# AnyKey.net
KiCad netlist of a schematic drawn in EAGLE
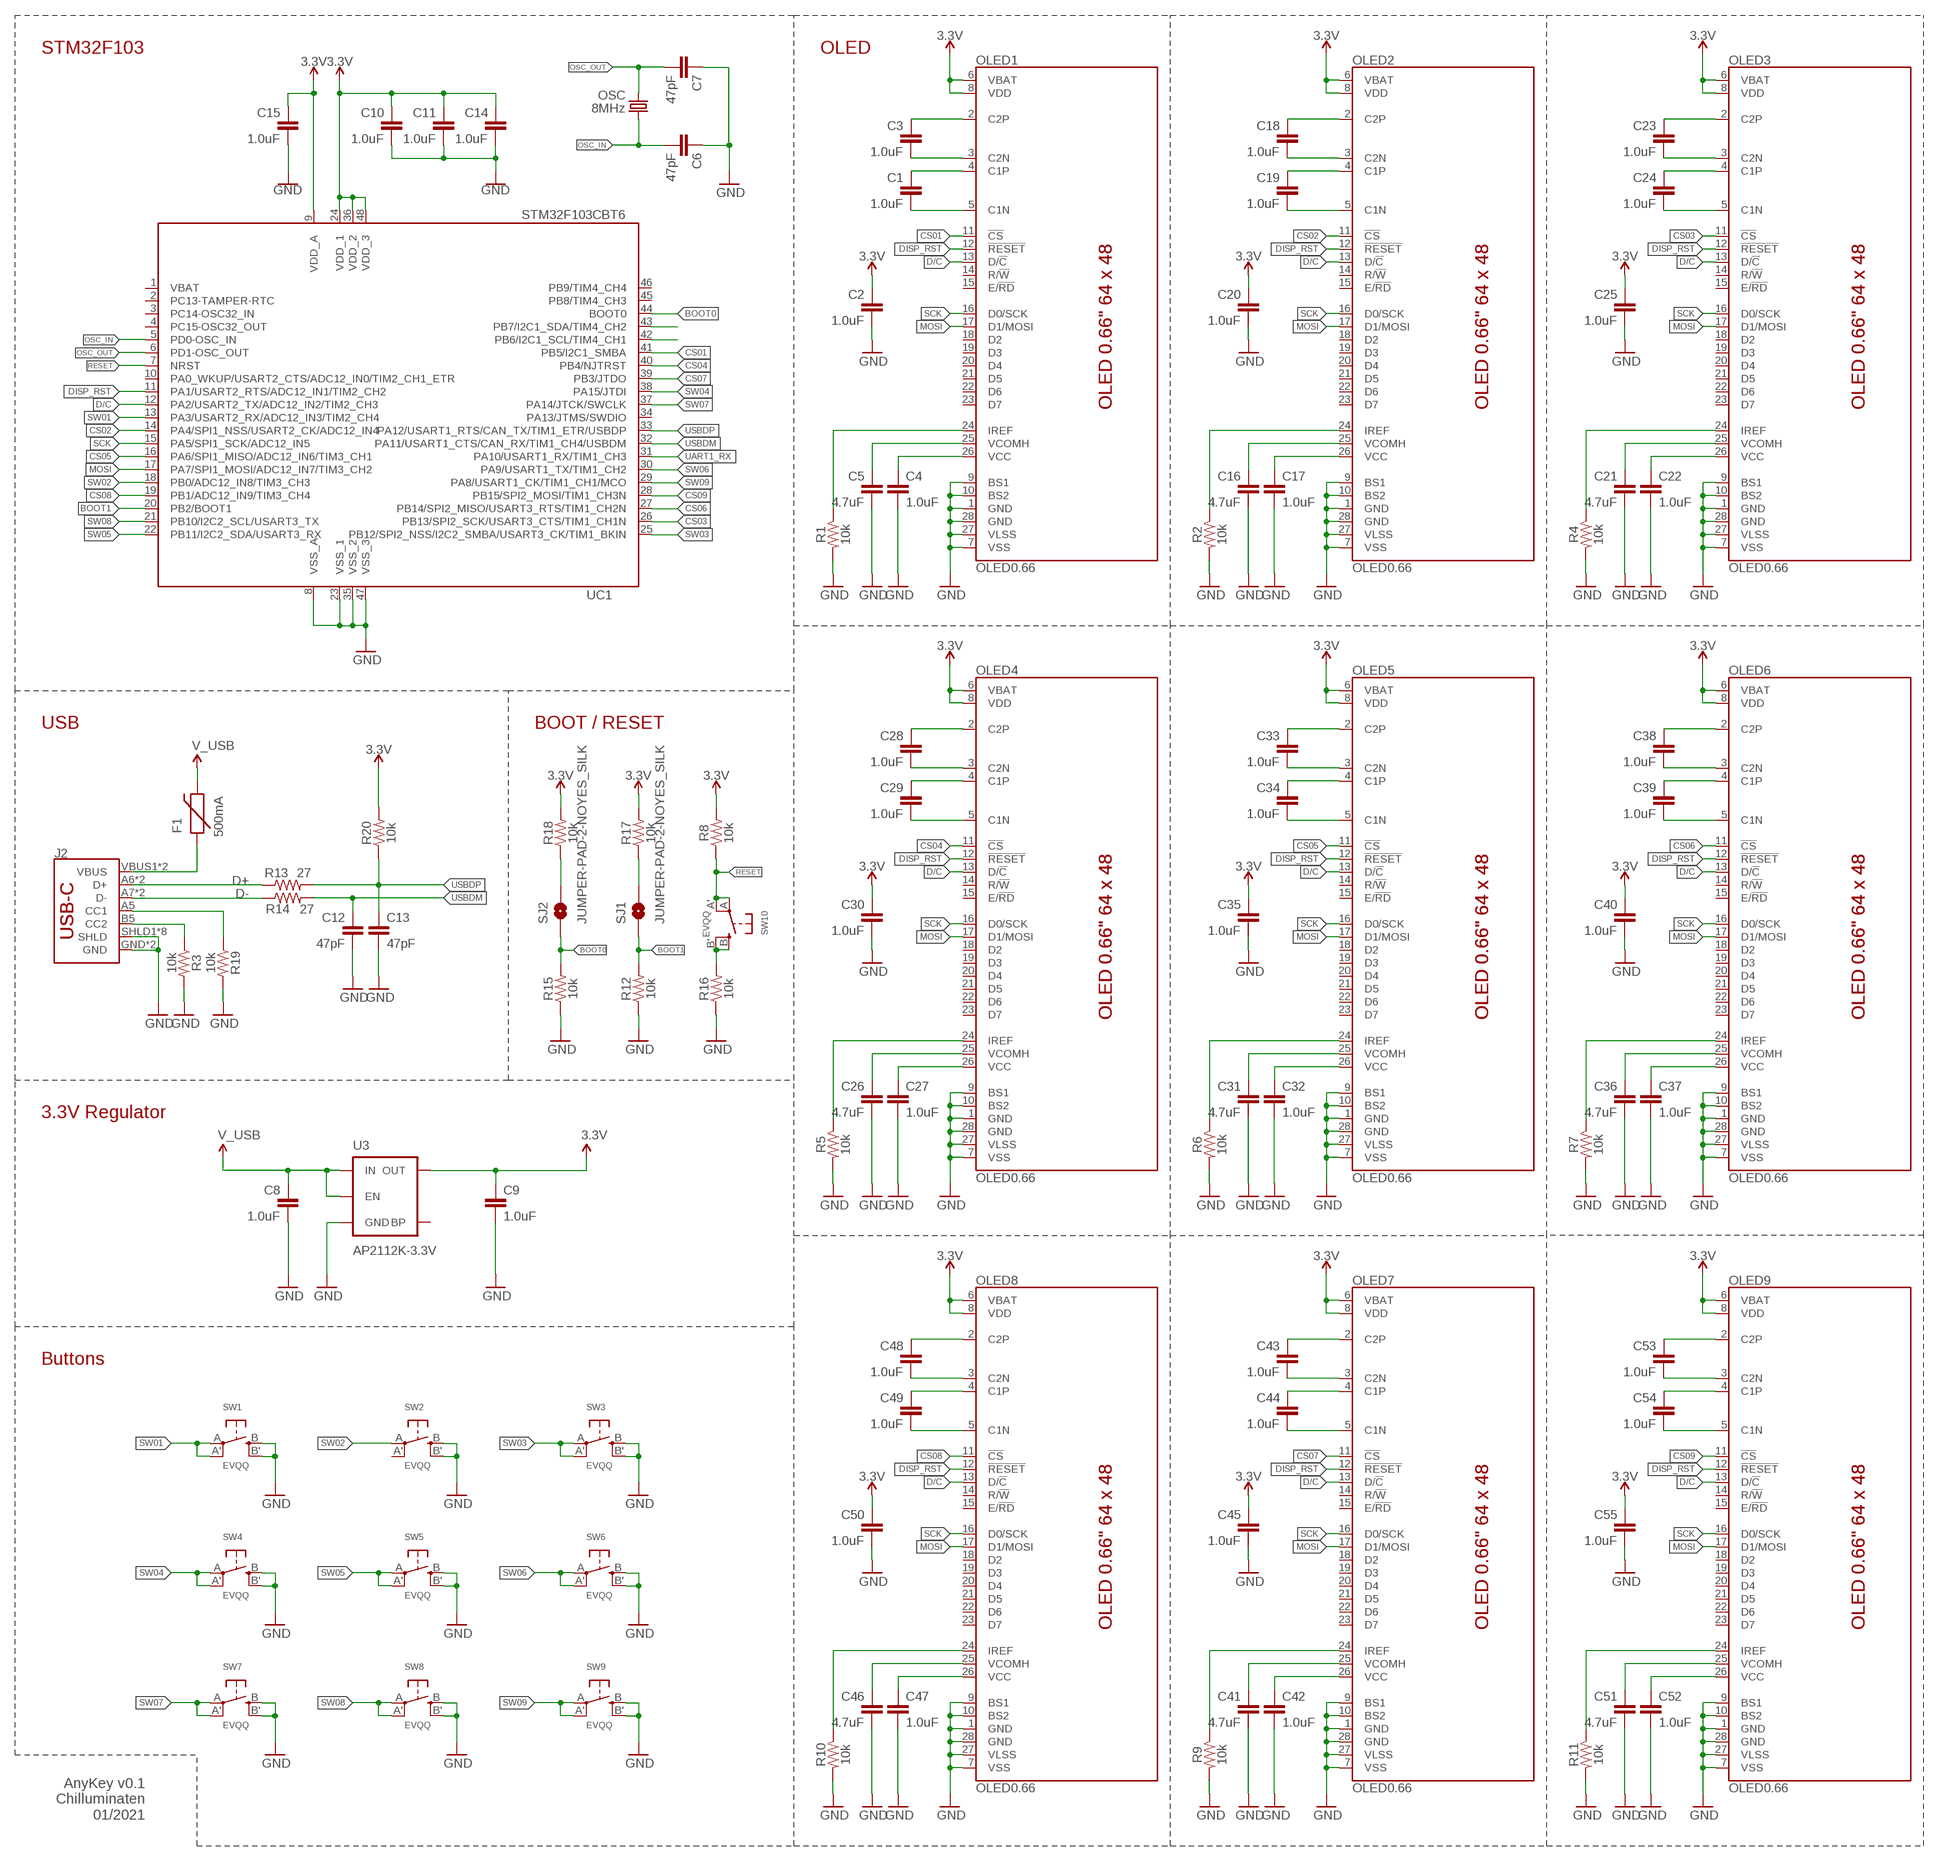
[diagram p0: schematic, sheet 1]

(export (version "E")
  (design (tool "Eeschema 10.0.6"))
  (components
    (comp (ref "C1")
      (value "1.0uF")
      (footprint "eagle-import:0805")
      (libsource (lib "eagle-import") (part "1.0UF-0805-25V-(+80/-20%)"))
    )
    (comp (ref "C2")
      (value "1.0uF")
      (footprint "eagle-import:0805")
      (libsource (lib "eagle-import") (part "1.0UF-0805-25V-(+80/-20%)"))
    )
    (comp (ref "C3")
      (value "1.0uF")
      (footprint "eagle-import:0805")
      (libsource (lib "eagle-import") (part "1.0UF-0805-25V-(+80/-20%)"))
    )
    (comp (ref "C4")
      (value "1.0uF")
      (footprint "eagle-import:0805")
      (libsource (lib "eagle-import") (part "1.0UF-0805-25V-(+80/-20%)"))
    )
    (comp (ref "C5")
      (value "4.7uF")
      (footprint "eagle-import:0603")
      (libsource (lib "eagle-import") (part "4.7UF0603"))
    )
    (comp (ref "C6")
      (value "47pF")
      (footprint "eagle-import:0603")
      (libsource (lib "eagle-import") (part "47PF-0603-50V-5%"))
    )
    (comp (ref "C7")
      (value "47pF")
      (footprint "eagle-import:0603")
      (libsource (lib "eagle-import") (part "47PF-0603-50V-5%"))
    )
    (comp (ref "C8")
      (value "1.0uF")
      (footprint "eagle-import:0805")
      (libsource (lib "eagle-import") (part "1.0UF-0805-25V-(+80/-20%)"))
    )
    (comp (ref "C9")
      (value "1.0uF")
      (footprint "eagle-import:0805")
      (libsource (lib "eagle-import") (part "1.0UF-0805-25V-(+80/-20%)"))
    )
    (comp (ref "C10")
      (value "1.0uF")
      (footprint "eagle-import:0805")
      (libsource (lib "eagle-import") (part "1.0UF-0805-25V-(+80/-20%)"))
    )
    (comp (ref "C11")
      (value "1.0uF")
      (footprint "eagle-import:0805")
      (libsource (lib "eagle-import") (part "1.0UF-0805-25V-(+80/-20%)"))
    )
    (comp (ref "C12")
      (value "47pF")
      (footprint "eagle-import:0603")
      (libsource (lib "eagle-import") (part "47PF-0603-50V-5%"))
    )
    (comp (ref "C13")
      (value "47pF")
      (footprint "eagle-import:0603")
      (libsource (lib "eagle-import") (part "47PF-0603-50V-5%"))
    )
    (comp (ref "C14")
      (value "1.0uF")
      (footprint "eagle-import:0805")
      (libsource (lib "eagle-import") (part "1.0UF-0805-25V-(+80/-20%)"))
    )
    (comp (ref "C15")
      (value "1.0uF")
      (footprint "eagle-import:0805")
      (libsource (lib "eagle-import") (part "1.0UF-0805-25V-(+80/-20%)"))
    )
    (comp (ref "C16")
      (value "4.7uF")
      (footprint "eagle-import:0603")
      (libsource (lib "eagle-import") (part "4.7UF0603"))
    )
    (comp (ref "C17")
      (value "1.0uF")
      (footprint "eagle-import:0805")
      (libsource (lib "eagle-import") (part "1.0UF-0805-25V-(+80/-20%)"))
    )
    (comp (ref "C18")
      (value "1.0uF")
      (footprint "eagle-import:0805")
      (libsource (lib "eagle-import") (part "1.0UF-0805-25V-(+80/-20%)"))
    )
    (comp (ref "C19")
      (value "1.0uF")
      (footprint "eagle-import:0805")
      (libsource (lib "eagle-import") (part "1.0UF-0805-25V-(+80/-20%)"))
    )
    (comp (ref "C20")
      (value "1.0uF")
      (footprint "eagle-import:0805")
      (libsource (lib "eagle-import") (part "1.0UF-0805-25V-(+80/-20%)"))
    )
    (comp (ref "C21")
      (value "4.7uF")
      (footprint "eagle-import:0603")
      (libsource (lib "eagle-import") (part "4.7UF0603"))
    )
    (comp (ref "C22")
      (value "1.0uF")
      (footprint "eagle-import:0805")
      (libsource (lib "eagle-import") (part "1.0UF-0805-25V-(+80/-20%)"))
    )
    (comp (ref "C23")
      (value "1.0uF")
      (footprint "eagle-import:0805")
      (libsource (lib "eagle-import") (part "1.0UF-0805-25V-(+80/-20%)"))
    )
    (comp (ref "C24")
      (value "1.0uF")
      (footprint "eagle-import:0805")
      (libsource (lib "eagle-import") (part "1.0UF-0805-25V-(+80/-20%)"))
    )
    (comp (ref "C25")
      (value "1.0uF")
      (footprint "eagle-import:0805")
      (libsource (lib "eagle-import") (part "1.0UF-0805-25V-(+80/-20%)"))
    )
    (comp (ref "C26")
      (value "4.7uF")
      (footprint "eagle-import:0603")
      (libsource (lib "eagle-import") (part "4.7UF0603"))
    )
    (comp (ref "C27")
      (value "1.0uF")
      (footprint "eagle-import:0805")
      (libsource (lib "eagle-import") (part "1.0UF-0805-25V-(+80/-20%)"))
    )
    (comp (ref "C28")
      (value "1.0uF")
      (footprint "eagle-import:0805")
      (libsource (lib "eagle-import") (part "1.0UF-0805-25V-(+80/-20%)"))
    )
    (comp (ref "C29")
      (value "1.0uF")
      (footprint "eagle-import:0805")
      (libsource (lib "eagle-import") (part "1.0UF-0805-25V-(+80/-20%)"))
    )
    (comp (ref "C30")
      (value "1.0uF")
      (footprint "eagle-import:0805")
      (libsource (lib "eagle-import") (part "1.0UF-0805-25V-(+80/-20%)"))
    )
    (comp (ref "C31")
      (value "4.7uF")
      (footprint "eagle-import:0603")
      (libsource (lib "eagle-import") (part "4.7UF0603"))
    )
    (comp (ref "C32")
      (value "1.0uF")
      (footprint "eagle-import:0805")
      (libsource (lib "eagle-import") (part "1.0UF-0805-25V-(+80/-20%)"))
    )
    (comp (ref "C33")
      (value "1.0uF")
      (footprint "eagle-import:0805")
      (libsource (lib "eagle-import") (part "1.0UF-0805-25V-(+80/-20%)"))
    )
    (comp (ref "C34")
      (value "1.0uF")
      (footprint "eagle-import:0805")
      (libsource (lib "eagle-import") (part "1.0UF-0805-25V-(+80/-20%)"))
    )
    (comp (ref "C35")
      (value "1.0uF")
      (footprint "eagle-import:0805")
      (libsource (lib "eagle-import") (part "1.0UF-0805-25V-(+80/-20%)"))
    )
    (comp (ref "C36")
      (value "4.7uF")
      (footprint "eagle-import:0603")
      (libsource (lib "eagle-import") (part "4.7UF0603"))
    )
    (comp (ref "C37")
      (value "1.0uF")
      (footprint "eagle-import:0805")
      (libsource (lib "eagle-import") (part "1.0UF-0805-25V-(+80/-20%)"))
    )
    (comp (ref "C38")
      (value "1.0uF")
      (footprint "eagle-import:0805")
      (libsource (lib "eagle-import") (part "1.0UF-0805-25V-(+80/-20%)"))
    )
    (comp (ref "C39")
      (value "1.0uF")
      (footprint "eagle-import:0805")
      (libsource (lib "eagle-import") (part "1.0UF-0805-25V-(+80/-20%)"))
    )
    (comp (ref "C40")
      (value "1.0uF")
      (footprint "eagle-import:0805")
      (libsource (lib "eagle-import") (part "1.0UF-0805-25V-(+80/-20%)"))
    )
    (comp (ref "C41")
      (value "4.7uF")
      (footprint "eagle-import:0603")
      (libsource (lib "eagle-import") (part "4.7UF0603"))
    )
    (comp (ref "C42")
      (value "1.0uF")
      (footprint "eagle-import:0805")
      (libsource (lib "eagle-import") (part "1.0UF-0805-25V-(+80/-20%)"))
    )
    (comp (ref "C43")
      (value "1.0uF")
      (footprint "eagle-import:0805")
      (libsource (lib "eagle-import") (part "1.0UF-0805-25V-(+80/-20%)"))
    )
    (comp (ref "C44")
      (value "1.0uF")
      (footprint "eagle-import:0805")
      (libsource (lib "eagle-import") (part "1.0UF-0805-25V-(+80/-20%)"))
    )
    (comp (ref "C45")
      (value "1.0uF")
      (footprint "eagle-import:0805")
      (libsource (lib "eagle-import") (part "1.0UF-0805-25V-(+80/-20%)"))
    )
    (comp (ref "C46")
      (value "4.7uF")
      (footprint "eagle-import:0603")
      (libsource (lib "eagle-import") (part "4.7UF0603"))
    )
    (comp (ref "C47")
      (value "1.0uF")
      (footprint "eagle-import:0805")
      (libsource (lib "eagle-import") (part "1.0UF-0805-25V-(+80/-20%)"))
    )
    (comp (ref "C48")
      (value "1.0uF")
      (footprint "eagle-import:0805")
      (libsource (lib "eagle-import") (part "1.0UF-0805-25V-(+80/-20%)"))
    )
    (comp (ref "C49")
      (value "1.0uF")
      (footprint "eagle-import:0805")
      (libsource (lib "eagle-import") (part "1.0UF-0805-25V-(+80/-20%)"))
    )
    (comp (ref "C50")
      (value "1.0uF")
      (footprint "eagle-import:0805")
      (libsource (lib "eagle-import") (part "1.0UF-0805-25V-(+80/-20%)"))
    )
    (comp (ref "C51")
      (value "4.7uF")
      (footprint "eagle-import:0603")
      (libsource (lib "eagle-import") (part "4.7UF0603"))
    )
    (comp (ref "C52")
      (value "1.0uF")
      (footprint "eagle-import:0805")
      (libsource (lib "eagle-import") (part "1.0UF-0805-25V-(+80/-20%)"))
    )
    (comp (ref "C53")
      (value "1.0uF")
      (footprint "eagle-import:0805")
      (libsource (lib "eagle-import") (part "1.0UF-0805-25V-(+80/-20%)"))
    )
    (comp (ref "C54")
      (value "1.0uF")
      (footprint "eagle-import:0805")
      (libsource (lib "eagle-import") (part "1.0UF-0805-25V-(+80/-20%)"))
    )
    (comp (ref "C55")
      (value "1.0uF")
      (footprint "eagle-import:0805")
      (libsource (lib "eagle-import") (part "1.0UF-0805-25V-(+80/-20%)"))
    )
    (comp (ref "F1")
      (value "500mA")
      (footprint "eagle-import:PTC-1206")
      (libsource (lib "eagle-import") (part "PTCSMD"))
    )
    (comp (ref "J2")
      (value "USB_C16PIN")
      (footprint "eagle-import:USB-C-16P")
      (libsource (lib "eagle-import") (part "USB_C16PIN"))
    )
    (comp (ref "OLED1")
      (value "OLED0.66")
      (footprint "eagle-import:OLED-0.66-64X48")
      (libsource (lib "eagle-import") (part "OLED0.66"))
    )
    (comp (ref "OLED2")
      (value "OLED0.66")
      (footprint "eagle-import:OLED-0.66-64X48")
      (libsource (lib "eagle-import") (part "OLED0.66"))
    )
    (comp (ref "OLED3")
      (value "OLED0.66")
      (footprint "eagle-import:OLED-0.66-64X48")
      (libsource (lib "eagle-import") (part "OLED0.66"))
    )
    (comp (ref "OLED4")
      (value "OLED0.66")
      (footprint "eagle-import:OLED-0.66-64X48")
      (libsource (lib "eagle-import") (part "OLED0.66"))
    )
    (comp (ref "OLED5")
      (value "OLED0.66")
      (footprint "eagle-import:OLED-0.66-64X48")
      (libsource (lib "eagle-import") (part "OLED0.66"))
    )
    (comp (ref "OLED6")
      (value "OLED0.66")
      (footprint "eagle-import:OLED-0.66-64X48")
      (libsource (lib "eagle-import") (part "OLED0.66"))
    )
    (comp (ref "OLED7")
      (value "OLED0.66")
      (footprint "eagle-import:OLED-0.66-64X48")
      (libsource (lib "eagle-import") (part "OLED0.66"))
    )
    (comp (ref "OLED8")
      (value "OLED0.66")
      (footprint "eagle-import:OLED-0.66-64X48")
      (libsource (lib "eagle-import") (part "OLED0.66"))
    )
    (comp (ref "OLED9")
      (value "OLED0.66")
      (footprint "eagle-import:OLED-0.66-64X48")
      (libsource (lib "eagle-import") (part "OLED0.66"))
    )
    (comp (ref "OSC")
      (value "8MHz")
      (footprint "eagle-import:CRYSTAL-SMD-5X3")
      (libsource (lib "eagle-import") (part "CRYSTAL5X3"))
    )
    (comp (ref "R1")
      (value "10k")
      (footprint "eagle-import:0603")
      (libsource (lib "eagle-import") (part "10KOHM-0603-1/10W-1%"))
    )
    (comp (ref "R2")
      (value "10k")
      (footprint "eagle-import:0603")
      (libsource (lib "eagle-import") (part "10KOHM-0603-1/10W-1%"))
    )
    (comp (ref "R3")
      (value "10k")
      (footprint "eagle-import:0603")
      (libsource (lib "eagle-import") (part "10KOHM-0603-1/10W-1%"))
    )
    (comp (ref "R4")
      (value "10k")
      (footprint "eagle-import:0603")
      (libsource (lib "eagle-import") (part "10KOHM-0603-1/10W-1%"))
    )
    (comp (ref "R5")
      (value "10k")
      (footprint "eagle-import:0603")
      (libsource (lib "eagle-import") (part "10KOHM-0603-1/10W-1%"))
    )
    (comp (ref "R6")
      (value "10k")
      (footprint "eagle-import:0603")
      (libsource (lib "eagle-import") (part "10KOHM-0603-1/10W-1%"))
    )
    (comp (ref "R7")
      (value "10k")
      (footprint "eagle-import:0603")
      (libsource (lib "eagle-import") (part "10KOHM-0603-1/10W-1%"))
    )
    (comp (ref "R8")
      (value "10k")
      (footprint "eagle-import:0603")
      (libsource (lib "eagle-import") (part "10KOHM-0603-1/10W-1%"))
    )
    (comp (ref "R9")
      (value "10k")
      (footprint "eagle-import:0603")
      (libsource (lib "eagle-import") (part "10KOHM-0603-1/10W-1%"))
    )
    (comp (ref "R10")
      (value "10k")
      (footprint "eagle-import:0603")
      (libsource (lib "eagle-import") (part "10KOHM-0603-1/10W-1%"))
    )
    (comp (ref "R11")
      (value "10k")
      (footprint "eagle-import:0603")
      (libsource (lib "eagle-import") (part "10KOHM-0603-1/10W-1%"))
    )
    (comp (ref "R12")
      (value "10k")
      (footprint "eagle-import:0603")
      (libsource (lib "eagle-import") (part "10KOHM-0603-1/10W-1%"))
    )
    (comp (ref "R13")
      (value "27")
      (footprint "eagle-import:0603")
      (libsource (lib "eagle-import") (part "27OHM1/10W1%(0603)0603-RES"))
    )
    (comp (ref "R14")
      (value "27")
      (footprint "eagle-import:0603")
      (libsource (lib "eagle-import") (part "27OHM1/10W1%(0603)0603-RES"))
    )
    (comp (ref "R15")
      (value "10k")
      (footprint "eagle-import:0603")
      (libsource (lib "eagle-import") (part "10KOHM-0603-1/10W-1%"))
    )
    (comp (ref "R16")
      (value "10k")
      (footprint "eagle-import:0603")
      (libsource (lib "eagle-import") (part "10KOHM-0603-1/10W-1%"))
    )
    (comp (ref "R17")
      (value "10k")
      (footprint "eagle-import:0603")
      (libsource (lib "eagle-import") (part "10KOHM-0603-1/10W-1%"))
    )
    (comp (ref "R18")
      (value "10k")
      (footprint "eagle-import:0603")
      (libsource (lib "eagle-import") (part "10KOHM-0603-1/10W-1%"))
    )
    (comp (ref "R19")
      (value "10k")
      (footprint "eagle-import:0603")
      (libsource (lib "eagle-import") (part "10KOHM-0603-1/10W-1%"))
    )
    (comp (ref "R20")
      (value "10k")
      (footprint "eagle-import:0603")
      (libsource (lib "eagle-import") (part "10KOHM-0603-1/10W-1%"))
    )
    (comp (ref "SJ1")
      (value "JUMPER-PAD-2-NOYES_SILK")
      (footprint "eagle-import:PAD-JUMPER-2-NO_YES_SILK")
      (libsource (lib "eagle-import") (part "JUMPER-PAD-2-NOYES_SILK"))
    )
    (comp (ref "SJ2")
      (value "JUMPER-PAD-2-NOYES_SILK")
      (footprint "eagle-import:PAD-JUMPER-2-NO_YES_SILK")
      (libsource (lib "eagle-import") (part "JUMPER-PAD-2-NOYES_SILK"))
    )
    (comp (ref "SW1")
      (value "EVQQ")
      (footprint "eagle-import:EVQ-Q2_SMALLER")
      (libsource (lib "eagle-import") (part "SWITCH_TACT_SMT_EVQQ2_SMALL"))
    )
    (comp (ref "SW2")
      (value "EVQQ")
      (footprint "eagle-import:EVQ-Q2_SMALLER")
      (libsource (lib "eagle-import") (part "SWITCH_TACT_SMT_EVQQ2_SMALL"))
    )
    (comp (ref "SW3")
      (value "EVQQ")
      (footprint "eagle-import:EVQ-Q2_SMALLER")
      (libsource (lib "eagle-import") (part "SWITCH_TACT_SMT_EVQQ2_SMALL"))
    )
    (comp (ref "SW4")
      (value "EVQQ")
      (footprint "eagle-import:EVQ-Q2_SMALLER")
      (libsource (lib "eagle-import") (part "SWITCH_TACT_SMT_EVQQ2_SMALL"))
    )
    (comp (ref "SW5")
      (value "EVQQ")
      (footprint "eagle-import:EVQ-Q2_SMALLER")
      (libsource (lib "eagle-import") (part "SWITCH_TACT_SMT_EVQQ2_SMALL"))
    )
    (comp (ref "SW6")
      (value "EVQQ")
      (footprint "eagle-import:EVQ-Q2_SMALLER")
      (libsource (lib "eagle-import") (part "SWITCH_TACT_SMT_EVQQ2_SMALL"))
    )
    (comp (ref "SW7")
      (value "EVQQ")
      (footprint "eagle-import:EVQ-Q2_SMALLER")
      (libsource (lib "eagle-import") (part "SWITCH_TACT_SMT_EVQQ2_SMALL"))
    )
    (comp (ref "SW8")
      (value "EVQQ")
      (footprint "eagle-import:EVQ-Q2_SMALLER")
      (libsource (lib "eagle-import") (part "SWITCH_TACT_SMT_EVQQ2_SMALL"))
    )
    (comp (ref "SW9")
      (value "EVQQ")
      (footprint "eagle-import:EVQ-Q2_SMALLER")
      (libsource (lib "eagle-import") (part "SWITCH_TACT_SMT_EVQQ2_SMALL"))
    )
    (comp (ref "SW10")
      (value "EVQQ")
      (footprint "eagle-import:EVQ-Q2_SMALLER")
      (libsource (lib "eagle-import") (part "SWITCH_TACT_SMT_EVQQ2_SMALL"))
    )
    (comp (ref "U3")
      (value "AP2112K-3.3V")
      (footprint "eagle-import:SOT23-5")
      (fields (field (name "PROD_ID") "VREG-12457"))
      (libsource (lib "eagle-import") (part "V_REG_LDOSMD"))
    )
    (comp (ref "UC1")
      (value "STM32F103CBT6")
      (footprint "eagle-import:LQFP48")
      (libsource (lib "eagle-import") (part "STM32F103CB"))
    )
  )
  (nets
    (net (code "1") (name "/D+") (class "Default")
      (node (ref "J2") (pin "A6") (pinfunction "D+_A6") (pintype "bidirectional"))
      (node (ref "J2") (pin "B6") (pinfunction "D+_B6") (pintype "bidirectional"))
      (node (ref "R13") (pin "1") (pinfunction "1_1") (pintype "passive"))
    )
    (net (code "2") (name "/D-") (class "Default")
      (node (ref "J2") (pin "A7") (pinfunction "D-_A7") (pintype "bidirectional"))
      (node (ref "J2") (pin "B7") (pinfunction "D-_B7") (pintype "bidirectional"))
      (node (ref "R14") (pin "1") (pinfunction "1_1") (pintype "passive"))
    )
    (net (code "3") (name "/VBAT") (class "Default")
      (node (ref "UC1") (pin "1") (pinfunction "VBAT_1") (pintype "power_in"))
    )
    (net (code "4") (name "3.3V") (class "Default")
      (node (ref "C10") (pin "1") (pinfunction "1_1") (pintype "passive"))
      (node (ref "C11") (pin "1") (pinfunction "1_1") (pintype "passive"))
      (node (ref "C14") (pin "1") (pinfunction "1_1") (pintype "passive"))
      (node (ref "C15") (pin "1") (pinfunction "1_1") (pintype "passive"))
      (node (ref "C2") (pin "1") (pinfunction "1_1") (pintype "passive"))
      (node (ref "C20") (pin "1") (pinfunction "1_1") (pintype "passive"))
      (node (ref "C25") (pin "1") (pinfunction "1_1") (pintype "passive"))
      (node (ref "C30") (pin "1") (pinfunction "1_1") (pintype "passive"))
      (node (ref "C35") (pin "1") (pinfunction "1_1") (pintype "passive"))
      (node (ref "C40") (pin "1") (pinfunction "1_1") (pintype "passive"))
      (node (ref "C45") (pin "1") (pinfunction "1_1") (pintype "passive"))
      (node (ref "C50") (pin "1") (pinfunction "1_1") (pintype "passive"))
      (node (ref "C55") (pin "1") (pinfunction "1_1") (pintype "passive"))
      (node (ref "C9") (pin "1") (pinfunction "1_1") (pintype "passive"))
      (node (ref "OLED1") (pin "6") (pinfunction "VBAT_6") (pintype "bidirectional"))
      (node (ref "OLED1") (pin "8") (pinfunction "VDD_8") (pintype "bidirectional"))
      (node (ref "OLED2") (pin "6") (pinfunction "VBAT_6") (pintype "bidirectional"))
      (node (ref "OLED2") (pin "8") (pinfunction "VDD_8") (pintype "bidirectional"))
      (node (ref "OLED3") (pin "6") (pinfunction "VBAT_6") (pintype "bidirectional"))
      (node (ref "OLED3") (pin "8") (pinfunction "VDD_8") (pintype "bidirectional"))
      (node (ref "OLED4") (pin "6") (pinfunction "VBAT_6") (pintype "bidirectional"))
      (node (ref "OLED4") (pin "8") (pinfunction "VDD_8") (pintype "bidirectional"))
      (node (ref "OLED5") (pin "6") (pinfunction "VBAT_6") (pintype "bidirectional"))
      (node (ref "OLED5") (pin "8") (pinfunction "VDD_8") (pintype "bidirectional"))
      (node (ref "OLED6") (pin "6") (pinfunction "VBAT_6") (pintype "bidirectional"))
      (node (ref "OLED6") (pin "8") (pinfunction "VDD_8") (pintype "bidirectional"))
      (node (ref "OLED7") (pin "6") (pinfunction "VBAT_6") (pintype "bidirectional"))
      (node (ref "OLED7") (pin "8") (pinfunction "VDD_8") (pintype "bidirectional"))
      (node (ref "OLED8") (pin "6") (pinfunction "VBAT_6") (pintype "bidirectional"))
      (node (ref "OLED8") (pin "8") (pinfunction "VDD_8") (pintype "bidirectional"))
      (node (ref "OLED9") (pin "6") (pinfunction "VBAT_6") (pintype "bidirectional"))
      (node (ref "OLED9") (pin "8") (pinfunction "VDD_8") (pintype "bidirectional"))
      (node (ref "R17") (pin "2") (pinfunction "2_2") (pintype "passive"))
      (node (ref "R18") (pin "2") (pinfunction "2_2") (pintype "passive"))
      (node (ref "R20") (pin "2") (pinfunction "2_2") (pintype "passive"))
      (node (ref "R8") (pin "2") (pinfunction "2_2") (pintype "passive"))
      (node (ref "U3") (pin "5") (pinfunction "OUT_5") (pintype "passive"))
      (node (ref "UC1") (pin "24") (pinfunction "VDD_1_24") (pintype "power_in"))
      (node (ref "UC1") (pin "36") (pinfunction "VDD_2_36") (pintype "power_in"))
      (node (ref "UC1") (pin "48") (pinfunction "VDD_3_48") (pintype "power_in"))
      (node (ref "UC1") (pin "9") (pinfunction "VDD_A_9") (pintype "power_in"))
    )
    (net (code "5") (name "BOOT0") (class "Default")
      (node (ref "R15") (pin "2") (pinfunction "2_2") (pintype "passive"))
      (node (ref "SJ2") (pin "1") (pinfunction "1_1") (pintype "passive"))
      (node (ref "UC1") (pin "44") (pinfunction "BOOT0_44") (pintype "input"))
    )
    (net (code "6") (name "BOOT1") (class "Default")
      (node (ref "R12") (pin "2") (pinfunction "2_2") (pintype "passive"))
      (node (ref "SJ1") (pin "1") (pinfunction "1_1") (pintype "passive"))
      (node (ref "UC1") (pin "20") (pinfunction "PB2/BOOT1_20") (pintype "bidirectional"))
    )
    (net (code "7") (name "CS01") (class "Default")
      (node (ref "OLED1") (pin "11") (pinfunction "~{CS}_11") (pintype "bidirectional"))
      (node (ref "UC1") (pin "41") (pinfunction "PB5/I2C1_SMBA_41") (pintype "input"))
    )
    (net (code "8") (name "CS02") (class "Default")
      (node (ref "OLED2") (pin "11") (pinfunction "~{CS}_11") (pintype "bidirectional"))
      (node (ref "UC1") (pin "14") (pinfunction "PA4/SPI1_NSS/USART2_CK/ADC12_IN4_14") (pintype "bidirectional"))
    )
    (net (code "9") (name "CS03") (class "Default")
      (node (ref "OLED3") (pin "11") (pinfunction "~{CS}_11") (pintype "bidirectional"))
      (node (ref "UC1") (pin "26") (pinfunction "PB13/SPI2_SCK/USART3_CTS/TIM1_CH1N_26") (pintype "input"))
    )
    (net (code "10") (name "CS04") (class "Default")
      (node (ref "OLED4") (pin "11") (pinfunction "~{CS}_11") (pintype "bidirectional"))
      (node (ref "UC1") (pin "40") (pinfunction "PB4/NJTRST_40") (pintype "bidirectional"))
    )
    (net (code "11") (name "CS05") (class "Default")
      (node (ref "OLED5") (pin "11") (pinfunction "~{CS}_11") (pintype "bidirectional"))
      (node (ref "UC1") (pin "16") (pinfunction "PA6/SPI1_MISO/ADC12_IN6/TIM3_CH1_16") (pintype "bidirectional"))
    )
    (net (code "12") (name "CS06") (class "Default")
      (node (ref "OLED6") (pin "11") (pinfunction "~{CS}_11") (pintype "bidirectional"))
      (node (ref "UC1") (pin "27") (pinfunction "PB14/SPI2_MISO/USART3_RTS/TIM1_CH2N_27") (pintype "input"))
    )
    (net (code "13") (name "CS07") (class "Default")
      (node (ref "OLED7") (pin "11") (pinfunction "~{CS}_11") (pintype "bidirectional"))
      (node (ref "UC1") (pin "39") (pinfunction "PB3/JTDO_39") (pintype "bidirectional"))
    )
    (net (code "14") (name "CS08") (class "Default")
      (node (ref "OLED8") (pin "11") (pinfunction "~{CS}_11") (pintype "bidirectional"))
      (node (ref "UC1") (pin "19") (pinfunction "PB1/ADC12_IN9/TIM3_CH4_19") (pintype "bidirectional"))
    )
    (net (code "15") (name "CS09") (class "Default")
      (node (ref "OLED9") (pin "11") (pinfunction "~{CS}_11") (pintype "bidirectional"))
      (node (ref "UC1") (pin "28") (pinfunction "PB15/SPI2_MOSI/TIM1_CH3N_28") (pintype "input"))
    )
    (net (code "16") (name "DISP_RST") (class "Default")
      (node (ref "OLED1") (pin "12") (pinfunction "~{RESET}_12") (pintype "bidirectional"))
      (node (ref "OLED2") (pin "12") (pinfunction "~{RESET}_12") (pintype "bidirectional"))
      (node (ref "OLED3") (pin "12") (pinfunction "~{RESET}_12") (pintype "bidirectional"))
      (node (ref "OLED4") (pin "12") (pinfunction "~{RESET}_12") (pintype "bidirectional"))
      (node (ref "OLED5") (pin "12") (pinfunction "~{RESET}_12") (pintype "bidirectional"))
      (node (ref "OLED6") (pin "12") (pinfunction "~{RESET}_12") (pintype "bidirectional"))
      (node (ref "OLED7") (pin "12") (pinfunction "~{RESET}_12") (pintype "bidirectional"))
      (node (ref "OLED8") (pin "12") (pinfunction "~{RESET}_12") (pintype "bidirectional"))
      (node (ref "OLED9") (pin "12") (pinfunction "~{RESET}_12") (pintype "bidirectional"))
      (node (ref "UC1") (pin "11") (pinfunction "PA1/USART2_RTS/ADC12_IN1/TIM2_CH2_11") (pintype "bidirectional"))
    )
    (net (code "17") (name "D{slash}C") (class "Default")
      (node (ref "OLED1") (pin "13") (pinfunction "D/~{C}_13") (pintype "bidirectional"))
      (node (ref "OLED2") (pin "13") (pinfunction "D/~{C}_13") (pintype "bidirectional"))
      (node (ref "OLED3") (pin "13") (pinfunction "D/~{C}_13") (pintype "bidirectional"))
      (node (ref "OLED4") (pin "13") (pinfunction "D/~{C}_13") (pintype "bidirectional"))
      (node (ref "OLED5") (pin "13") (pinfunction "D/~{C}_13") (pintype "bidirectional"))
      (node (ref "OLED6") (pin "13") (pinfunction "D/~{C}_13") (pintype "bidirectional"))
      (node (ref "OLED7") (pin "13") (pinfunction "D/~{C}_13") (pintype "bidirectional"))
      (node (ref "OLED8") (pin "13") (pinfunction "D/~{C}_13") (pintype "bidirectional"))
      (node (ref "OLED9") (pin "13") (pinfunction "D/~{C}_13") (pintype "bidirectional"))
      (node (ref "UC1") (pin "12") (pinfunction "PA2/USART2_TX/ADC12_IN2/TIM2_CH3_12") (pintype "bidirectional"))
    )
    (net (code "18") (name "GND") (class "Default")
      (node (ref "C10") (pin "2") (pinfunction "2_2") (pintype "passive"))
      (node (ref "C11") (pin "2") (pinfunction "2_2") (pintype "passive"))
      (node (ref "C12") (pin "2") (pinfunction "2_2") (pintype "passive"))
      (node (ref "C13") (pin "2") (pinfunction "2_2") (pintype "passive"))
      (node (ref "C14") (pin "2") (pinfunction "2_2") (pintype "passive"))
      (node (ref "C15") (pin "2") (pinfunction "2_2") (pintype "passive"))
      (node (ref "C16") (pin "2") (pinfunction "2_2") (pintype "passive"))
      (node (ref "C17") (pin "2") (pinfunction "2_2") (pintype "passive"))
      (node (ref "C2") (pin "2") (pinfunction "2_2") (pintype "passive"))
      (node (ref "C20") (pin "2") (pinfunction "2_2") (pintype "passive"))
      (node (ref "C21") (pin "2") (pinfunction "2_2") (pintype "passive"))
      (node (ref "C22") (pin "2") (pinfunction "2_2") (pintype "passive"))
      (node (ref "C25") (pin "2") (pinfunction "2_2") (pintype "passive"))
      (node (ref "C26") (pin "2") (pinfunction "2_2") (pintype "passive"))
      (node (ref "C27") (pin "2") (pinfunction "2_2") (pintype "passive"))
      (node (ref "C30") (pin "2") (pinfunction "2_2") (pintype "passive"))
      (node (ref "C31") (pin "2") (pinfunction "2_2") (pintype "passive"))
      (node (ref "C32") (pin "2") (pinfunction "2_2") (pintype "passive"))
      (node (ref "C35") (pin "2") (pinfunction "2_2") (pintype "passive"))
      (node (ref "C36") (pin "2") (pinfunction "2_2") (pintype "passive"))
      (node (ref "C37") (pin "2") (pinfunction "2_2") (pintype "passive"))
      (node (ref "C4") (pin "2") (pinfunction "2_2") (pintype "passive"))
      (node (ref "C40") (pin "2") (pinfunction "2_2") (pintype "passive"))
      (node (ref "C41") (pin "2") (pinfunction "2_2") (pintype "passive"))
      (node (ref "C42") (pin "2") (pinfunction "2_2") (pintype "passive"))
      (node (ref "C45") (pin "2") (pinfunction "2_2") (pintype "passive"))
      (node (ref "C46") (pin "2") (pinfunction "2_2") (pintype "passive"))
      (node (ref "C47") (pin "2") (pinfunction "2_2") (pintype "passive"))
      (node (ref "C5") (pin "2") (pinfunction "2_2") (pintype "passive"))
      (node (ref "C50") (pin "2") (pinfunction "2_2") (pintype "passive"))
      (node (ref "C51") (pin "2") (pinfunction "2_2") (pintype "passive"))
      (node (ref "C52") (pin "2") (pinfunction "2_2") (pintype "passive"))
      (node (ref "C55") (pin "2") (pinfunction "2_2") (pintype "passive"))
      (node (ref "C6") (pin "1") (pinfunction "1_1") (pintype "passive"))
      (node (ref "C7") (pin "1") (pinfunction "1_1") (pintype "passive"))
      (node (ref "C8") (pin "2") (pinfunction "2_2") (pintype "passive"))
      (node (ref "C9") (pin "2") (pinfunction "2_2") (pintype "passive"))
      (node (ref "J2") (pin "GND") (pinfunction "GND_GND") (pintype "bidirectional"))
      (node (ref "J2") (pin "GND2") (pinfunction "GND_GND2") (pintype "bidirectional"))
      (node (ref "J2") (pin "SHLD1") (pinfunction "SHLD_SHLD1") (pintype "bidirectional"))
      (node (ref "J2") (pin "SHLD2") (pinfunction "SHLD_SHLD2") (pintype "bidirectional"))
      (node (ref "J2") (pin "SHLD3") (pinfunction "SHLD_SHLD3") (pintype "bidirectional"))
      (node (ref "J2") (pin "SHLD4") (pinfunction "SHLD_SHLD4") (pintype "bidirectional"))
      (node (ref "J2") (pin "SHLD5") (pinfunction "SHLD_SHLD5") (pintype "bidirectional"))
      (node (ref "J2") (pin "SHLD6") (pinfunction "SHLD_SHLD6") (pintype "bidirectional"))
      (node (ref "J2") (pin "SHLD7") (pinfunction "SHLD_SHLD7") (pintype "bidirectional"))
      (node (ref "J2") (pin "SHLD8") (pinfunction "SHLD_SHLD8") (pintype "bidirectional"))
      (node (ref "OLED1") (pin "1") (pinfunction "GND_1") (pintype "bidirectional"))
      (node (ref "OLED1") (pin "10") (pinfunction "BS2_10") (pintype "bidirectional"))
      (node (ref "OLED1") (pin "27") (pinfunction "VLSS_27") (pintype "bidirectional"))
      (node (ref "OLED1") (pin "28") (pinfunction "GND_28") (pintype "bidirectional"))
      (node (ref "OLED1") (pin "7") (pinfunction "VSS_7") (pintype "bidirectional"))
      (node (ref "OLED1") (pin "9") (pinfunction "BS1_9") (pintype "bidirectional"))
      (node (ref "OLED2") (pin "1") (pinfunction "GND_1") (pintype "bidirectional"))
      (node (ref "OLED2") (pin "10") (pinfunction "BS2_10") (pintype "bidirectional"))
      (node (ref "OLED2") (pin "27") (pinfunction "VLSS_27") (pintype "bidirectional"))
      (node (ref "OLED2") (pin "28") (pinfunction "GND_28") (pintype "bidirectional"))
      (node (ref "OLED2") (pin "7") (pinfunction "VSS_7") (pintype "bidirectional"))
      (node (ref "OLED2") (pin "9") (pinfunction "BS1_9") (pintype "bidirectional"))
      (node (ref "OLED3") (pin "1") (pinfunction "GND_1") (pintype "bidirectional"))
      (node (ref "OLED3") (pin "10") (pinfunction "BS2_10") (pintype "bidirectional"))
      (node (ref "OLED3") (pin "27") (pinfunction "VLSS_27") (pintype "bidirectional"))
      (node (ref "OLED3") (pin "28") (pinfunction "GND_28") (pintype "bidirectional"))
      (node (ref "OLED3") (pin "7") (pinfunction "VSS_7") (pintype "bidirectional"))
      (node (ref "OLED3") (pin "9") (pinfunction "BS1_9") (pintype "bidirectional"))
      (node (ref "OLED4") (pin "1") (pinfunction "GND_1") (pintype "bidirectional"))
      (node (ref "OLED4") (pin "10") (pinfunction "BS2_10") (pintype "bidirectional"))
      (node (ref "OLED4") (pin "27") (pinfunction "VLSS_27") (pintype "bidirectional"))
      (node (ref "OLED4") (pin "28") (pinfunction "GND_28") (pintype "bidirectional"))
      (node (ref "OLED4") (pin "7") (pinfunction "VSS_7") (pintype "bidirectional"))
      (node (ref "OLED4") (pin "9") (pinfunction "BS1_9") (pintype "bidirectional"))
      (node (ref "OLED5") (pin "1") (pinfunction "GND_1") (pintype "bidirectional"))
      (node (ref "OLED5") (pin "10") (pinfunction "BS2_10") (pintype "bidirectional"))
      (node (ref "OLED5") (pin "27") (pinfunction "VLSS_27") (pintype "bidirectional"))
      (node (ref "OLED5") (pin "28") (pinfunction "GND_28") (pintype "bidirectional"))
      (node (ref "OLED5") (pin "7") (pinfunction "VSS_7") (pintype "bidirectional"))
      (node (ref "OLED5") (pin "9") (pinfunction "BS1_9") (pintype "bidirectional"))
      (node (ref "OLED6") (pin "1") (pinfunction "GND_1") (pintype "bidirectional"))
      (node (ref "OLED6") (pin "10") (pinfunction "BS2_10") (pintype "bidirectional"))
      (node (ref "OLED6") (pin "27") (pinfunction "VLSS_27") (pintype "bidirectional"))
      (node (ref "OLED6") (pin "28") (pinfunction "GND_28") (pintype "bidirectional"))
      (node (ref "OLED6") (pin "7") (pinfunction "VSS_7") (pintype "bidirectional"))
      (node (ref "OLED6") (pin "9") (pinfunction "BS1_9") (pintype "bidirectional"))
      (node (ref "OLED7") (pin "1") (pinfunction "GND_1") (pintype "bidirectional"))
      (node (ref "OLED7") (pin "10") (pinfunction "BS2_10") (pintype "bidirectional"))
      (node (ref "OLED7") (pin "27") (pinfunction "VLSS_27") (pintype "bidirectional"))
      (node (ref "OLED7") (pin "28") (pinfunction "GND_28") (pintype "bidirectional"))
      (node (ref "OLED7") (pin "7") (pinfunction "VSS_7") (pintype "bidirectional"))
      (node (ref "OLED7") (pin "9") (pinfunction "BS1_9") (pintype "bidirectional"))
      (node (ref "OLED8") (pin "1") (pinfunction "GND_1") (pintype "bidirectional"))
      (node (ref "OLED8") (pin "10") (pinfunction "BS2_10") (pintype "bidirectional"))
      (node (ref "OLED8") (pin "27") (pinfunction "VLSS_27") (pintype "bidirectional"))
      (node (ref "OLED8") (pin "28") (pinfunction "GND_28") (pintype "bidirectional"))
      (node (ref "OLED8") (pin "7") (pinfunction "VSS_7") (pintype "bidirectional"))
      (node (ref "OLED8") (pin "9") (pinfunction "BS1_9") (pintype "bidirectional"))
      (node (ref "OLED9") (pin "1") (pinfunction "GND_1") (pintype "bidirectional"))
      (node (ref "OLED9") (pin "10") (pinfunction "BS2_10") (pintype "bidirectional"))
      (node (ref "OLED9") (pin "27") (pinfunction "VLSS_27") (pintype "bidirectional"))
      (node (ref "OLED9") (pin "28") (pinfunction "GND_28") (pintype "bidirectional"))
      (node (ref "OLED9") (pin "7") (pinfunction "VSS_7") (pintype "bidirectional"))
      (node (ref "OLED9") (pin "9") (pinfunction "BS1_9") (pintype "bidirectional"))
      (node (ref "R1") (pin "2") (pinfunction "2_2") (pintype "passive"))
      (node (ref "R10") (pin "2") (pinfunction "2_2") (pintype "passive"))
      (node (ref "R11") (pin "2") (pinfunction "2_2") (pintype "passive"))
      (node (ref "R12") (pin "1") (pinfunction "1_1") (pintype "passive"))
      (node (ref "R15") (pin "1") (pinfunction "1_1") (pintype "passive"))
      (node (ref "R16") (pin "1") (pinfunction "1_1") (pintype "passive"))
      (node (ref "R19") (pin "2") (pinfunction "2_2") (pintype "passive"))
      (node (ref "R2") (pin "2") (pinfunction "2_2") (pintype "passive"))
      (node (ref "R3") (pin "2") (pinfunction "2_2") (pintype "passive"))
      (node (ref "R4") (pin "2") (pinfunction "2_2") (pintype "passive"))
      (node (ref "R5") (pin "2") (pinfunction "2_2") (pintype "passive"))
      (node (ref "R6") (pin "2") (pinfunction "2_2") (pintype "passive"))
      (node (ref "R7") (pin "2") (pinfunction "2_2") (pintype "passive"))
      (node (ref "R9") (pin "2") (pinfunction "2_2") (pintype "passive"))
      (node (ref "SW1") (pin "B") (pinfunction "S_B") (pintype "passive"))
      (node (ref "SW1") (pin "B'") (pinfunction "S1_B'") (pintype "passive"))
      (node (ref "SW2") (pin "B") (pinfunction "S_B") (pintype "passive"))
      (node (ref "SW2") (pin "B'") (pinfunction "S1_B'") (pintype "passive"))
      (node (ref "SW3") (pin "B") (pinfunction "S_B") (pintype "passive"))
      (node (ref "SW3") (pin "B'") (pinfunction "S1_B'") (pintype "passive"))
      (node (ref "SW4") (pin "B") (pinfunction "S_B") (pintype "passive"))
      (node (ref "SW4") (pin "B'") (pinfunction "S1_B'") (pintype "passive"))
      (node (ref "SW5") (pin "B") (pinfunction "S_B") (pintype "passive"))
      (node (ref "SW5") (pin "B'") (pinfunction "S1_B'") (pintype "passive"))
      (node (ref "SW6") (pin "B") (pinfunction "S_B") (pintype "passive"))
      (node (ref "SW6") (pin "B'") (pinfunction "S1_B'") (pintype "passive"))
      (node (ref "SW7") (pin "B") (pinfunction "S_B") (pintype "passive"))
      (node (ref "SW7") (pin "B'") (pinfunction "S1_B'") (pintype "passive"))
      (node (ref "SW8") (pin "B") (pinfunction "S_B") (pintype "passive"))
      (node (ref "SW8") (pin "B'") (pinfunction "S1_B'") (pintype "passive"))
      (node (ref "SW9") (pin "B") (pinfunction "S_B") (pintype "passive"))
      (node (ref "SW9") (pin "B'") (pinfunction "S1_B'") (pintype "passive"))
      (node (ref "U3") (pin "2") (pinfunction "GND_2") (pintype "input"))
      (node (ref "UC1") (pin "23") (pinfunction "VSS_1_23") (pintype "power_in"))
      (node (ref "UC1") (pin "35") (pinfunction "VSS_2_35") (pintype "power_in"))
      (node (ref "UC1") (pin "47") (pinfunction "VSS_3_47") (pintype "power_in"))
      (node (ref "UC1") (pin "8") (pinfunction "VSS_A_8") (pintype "power_in"))
    )
    (net (code "19") (name "MOSI") (class "Default")
      (node (ref "OLED1") (pin "17") (pinfunction "D1/MOSI_17") (pintype "bidirectional"))
      (node (ref "OLED2") (pin "17") (pinfunction "D1/MOSI_17") (pintype "bidirectional"))
      (node (ref "OLED3") (pin "17") (pinfunction "D1/MOSI_17") (pintype "bidirectional"))
      (node (ref "OLED4") (pin "17") (pinfunction "D1/MOSI_17") (pintype "bidirectional"))
      (node (ref "OLED5") (pin "17") (pinfunction "D1/MOSI_17") (pintype "bidirectional"))
      (node (ref "OLED6") (pin "17") (pinfunction "D1/MOSI_17") (pintype "bidirectional"))
      (node (ref "OLED7") (pin "17") (pinfunction "D1/MOSI_17") (pintype "bidirectional"))
      (node (ref "OLED8") (pin "17") (pinfunction "D1/MOSI_17") (pintype "bidirectional"))
      (node (ref "OLED9") (pin "17") (pinfunction "D1/MOSI_17") (pintype "bidirectional"))
      (node (ref "UC1") (pin "17") (pinfunction "PA7/SPI1_MOSI/ADC12_IN7/TIM3_CH2_17") (pintype "bidirectional"))
    )
    (net (code "20") (name "Net-(F1-Pad1)") (class "Default")
      (node (ref "F1") (pin "1") (pinfunction "1_1") (pintype "bidirectional"))
      (node (ref "J2") (pin "VBUS1") (pinfunction "VBUS_VBUS1") (pintype "bidirectional"))
      (node (ref "J2") (pin "VBUS2") (pinfunction "VBUS_VBUS2") (pintype "bidirectional"))
    )
    (net (code "21") (name "Net-(J2-CC1)") (class "Default")
      (node (ref "J2") (pin "A5") (pinfunction "CC1_A5") (pintype "bidirectional"))
      (node (ref "R19") (pin "1") (pinfunction "1_1") (pintype "passive"))
    )
    (net (code "22") (name "Net-(J2-CC2)") (class "Default")
      (node (ref "J2") (pin "B5") (pinfunction "CC2_B5") (pintype "bidirectional"))
      (node (ref "R3") (pin "1") (pinfunction "1_1") (pintype "passive"))
    )
    (net (code "23") (name "Net-(OLED1-C1N)") (class "Default")
      (node (ref "C1") (pin "2") (pinfunction "2_2") (pintype "passive"))
      (node (ref "OLED1") (pin "5") (pinfunction "C1N_5") (pintype "bidirectional"))
    )
    (net (code "24") (name "Net-(OLED1-C1P)") (class "Default")
      (node (ref "C1") (pin "1") (pinfunction "1_1") (pintype "passive"))
      (node (ref "OLED1") (pin "4") (pinfunction "C1P_4") (pintype "bidirectional"))
    )
    (net (code "25") (name "Net-(OLED1-C2N)") (class "Default")
      (node (ref "C3") (pin "2") (pinfunction "2_2") (pintype "passive"))
      (node (ref "OLED1") (pin "3") (pinfunction "C2N_3") (pintype "bidirectional"))
    )
    (net (code "26") (name "Net-(OLED1-C2P)") (class "Default")
      (node (ref "C3") (pin "1") (pinfunction "1_1") (pintype "passive"))
      (node (ref "OLED1") (pin "2") (pinfunction "C2P_2") (pintype "bidirectional"))
    )
    (net (code "27") (name "Net-(OLED1-IREF)") (class "Default")
      (node (ref "OLED1") (pin "24") (pinfunction "IREF_24") (pintype "bidirectional"))
      (node (ref "R1") (pin "1") (pinfunction "1_1") (pintype "passive"))
    )
    (net (code "28") (name "Net-(OLED1-VCC)") (class "Default")
      (node (ref "C4") (pin "1") (pinfunction "1_1") (pintype "passive"))
      (node (ref "OLED1") (pin "26") (pinfunction "VCC_26") (pintype "bidirectional"))
    )
    (net (code "29") (name "Net-(OLED1-VCOMH)") (class "Default")
      (node (ref "C5") (pin "1") (pinfunction "1_1") (pintype "passive"))
      (node (ref "OLED1") (pin "25") (pinfunction "VCOMH_25") (pintype "bidirectional"))
    )
    (net (code "30") (name "Net-(OLED2-C1N)") (class "Default")
      (node (ref "C19") (pin "2") (pinfunction "2_2") (pintype "passive"))
      (node (ref "OLED2") (pin "5") (pinfunction "C1N_5") (pintype "bidirectional"))
    )
    (net (code "31") (name "Net-(OLED2-C1P)") (class "Default")
      (node (ref "C19") (pin "1") (pinfunction "1_1") (pintype "passive"))
      (node (ref "OLED2") (pin "4") (pinfunction "C1P_4") (pintype "bidirectional"))
    )
    (net (code "32") (name "Net-(OLED2-C2N)") (class "Default")
      (node (ref "C18") (pin "2") (pinfunction "2_2") (pintype "passive"))
      (node (ref "OLED2") (pin "3") (pinfunction "C2N_3") (pintype "bidirectional"))
    )
    (net (code "33") (name "Net-(OLED2-C2P)") (class "Default")
      (node (ref "C18") (pin "1") (pinfunction "1_1") (pintype "passive"))
      (node (ref "OLED2") (pin "2") (pinfunction "C2P_2") (pintype "bidirectional"))
    )
    (net (code "34") (name "Net-(OLED2-IREF)") (class "Default")
      (node (ref "OLED2") (pin "24") (pinfunction "IREF_24") (pintype "bidirectional"))
      (node (ref "R2") (pin "1") (pinfunction "1_1") (pintype "passive"))
    )
    (net (code "35") (name "Net-(OLED2-VCC)") (class "Default")
      (node (ref "C17") (pin "1") (pinfunction "1_1") (pintype "passive"))
      (node (ref "OLED2") (pin "26") (pinfunction "VCC_26") (pintype "bidirectional"))
    )
    (net (code "36") (name "Net-(OLED2-VCOMH)") (class "Default")
      (node (ref "C16") (pin "1") (pinfunction "1_1") (pintype "passive"))
      (node (ref "OLED2") (pin "25") (pinfunction "VCOMH_25") (pintype "bidirectional"))
    )
    (net (code "37") (name "Net-(OLED3-C1N)") (class "Default")
      (node (ref "C24") (pin "2") (pinfunction "2_2") (pintype "passive"))
      (node (ref "OLED3") (pin "5") (pinfunction "C1N_5") (pintype "bidirectional"))
    )
    (net (code "38") (name "Net-(OLED3-C1P)") (class "Default")
      (node (ref "C24") (pin "1") (pinfunction "1_1") (pintype "passive"))
      (node (ref "OLED3") (pin "4") (pinfunction "C1P_4") (pintype "bidirectional"))
    )
    (net (code "39") (name "Net-(OLED3-C2N)") (class "Default")
      (node (ref "C23") (pin "2") (pinfunction "2_2") (pintype "passive"))
      (node (ref "OLED3") (pin "3") (pinfunction "C2N_3") (pintype "bidirectional"))
    )
    (net (code "40") (name "Net-(OLED3-C2P)") (class "Default")
      (node (ref "C23") (pin "1") (pinfunction "1_1") (pintype "passive"))
      (node (ref "OLED3") (pin "2") (pinfunction "C2P_2") (pintype "bidirectional"))
    )
    (net (code "41") (name "Net-(OLED3-IREF)") (class "Default")
      (node (ref "OLED3") (pin "24") (pinfunction "IREF_24") (pintype "bidirectional"))
      (node (ref "R4") (pin "1") (pinfunction "1_1") (pintype "passive"))
    )
    (net (code "42") (name "Net-(OLED3-VCC)") (class "Default")
      (node (ref "C22") (pin "1") (pinfunction "1_1") (pintype "passive"))
      (node (ref "OLED3") (pin "26") (pinfunction "VCC_26") (pintype "bidirectional"))
    )
    (net (code "43") (name "Net-(OLED3-VCOMH)") (class "Default")
      (node (ref "C21") (pin "1") (pinfunction "1_1") (pintype "passive"))
      (node (ref "OLED3") (pin "25") (pinfunction "VCOMH_25") (pintype "bidirectional"))
    )
    (net (code "44") (name "Net-(OLED4-C1N)") (class "Default")
      (node (ref "C29") (pin "2") (pinfunction "2_2") (pintype "passive"))
      (node (ref "OLED4") (pin "5") (pinfunction "C1N_5") (pintype "bidirectional"))
    )
    (net (code "45") (name "Net-(OLED4-C1P)") (class "Default")
      (node (ref "C29") (pin "1") (pinfunction "1_1") (pintype "passive"))
      (node (ref "OLED4") (pin "4") (pinfunction "C1P_4") (pintype "bidirectional"))
    )
    (net (code "46") (name "Net-(OLED4-C2N)") (class "Default")
      (node (ref "C28") (pin "2") (pinfunction "2_2") (pintype "passive"))
      (node (ref "OLED4") (pin "3") (pinfunction "C2N_3") (pintype "bidirectional"))
    )
    (net (code "47") (name "Net-(OLED4-C2P)") (class "Default")
      (node (ref "C28") (pin "1") (pinfunction "1_1") (pintype "passive"))
      (node (ref "OLED4") (pin "2") (pinfunction "C2P_2") (pintype "bidirectional"))
    )
    (net (code "48") (name "Net-(OLED4-IREF)") (class "Default")
      (node (ref "OLED4") (pin "24") (pinfunction "IREF_24") (pintype "bidirectional"))
      (node (ref "R5") (pin "1") (pinfunction "1_1") (pintype "passive"))
    )
    (net (code "49") (name "Net-(OLED4-VCC)") (class "Default")
      (node (ref "C27") (pin "1") (pinfunction "1_1") (pintype "passive"))
      (node (ref "OLED4") (pin "26") (pinfunction "VCC_26") (pintype "bidirectional"))
    )
    (net (code "50") (name "Net-(OLED4-VCOMH)") (class "Default")
      (node (ref "C26") (pin "1") (pinfunction "1_1") (pintype "passive"))
      (node (ref "OLED4") (pin "25") (pinfunction "VCOMH_25") (pintype "bidirectional"))
    )
    (net (code "51") (name "Net-(OLED5-C1N)") (class "Default")
      (node (ref "C34") (pin "2") (pinfunction "2_2") (pintype "passive"))
      (node (ref "OLED5") (pin "5") (pinfunction "C1N_5") (pintype "bidirectional"))
    )
    (net (code "52") (name "Net-(OLED5-C1P)") (class "Default")
      (node (ref "C34") (pin "1") (pinfunction "1_1") (pintype "passive"))
      (node (ref "OLED5") (pin "4") (pinfunction "C1P_4") (pintype "bidirectional"))
    )
    (net (code "53") (name "Net-(OLED5-C2N)") (class "Default")
      (node (ref "C33") (pin "2") (pinfunction "2_2") (pintype "passive"))
      (node (ref "OLED5") (pin "3") (pinfunction "C2N_3") (pintype "bidirectional"))
    )
    (net (code "54") (name "Net-(OLED5-C2P)") (class "Default")
      (node (ref "C33") (pin "1") (pinfunction "1_1") (pintype "passive"))
      (node (ref "OLED5") (pin "2") (pinfunction "C2P_2") (pintype "bidirectional"))
    )
    (net (code "55") (name "Net-(OLED5-IREF)") (class "Default")
      (node (ref "OLED5") (pin "24") (pinfunction "IREF_24") (pintype "bidirectional"))
      (node (ref "R6") (pin "1") (pinfunction "1_1") (pintype "passive"))
    )
    (net (code "56") (name "Net-(OLED5-VCC)") (class "Default")
      (node (ref "C32") (pin "1") (pinfunction "1_1") (pintype "passive"))
      (node (ref "OLED5") (pin "26") (pinfunction "VCC_26") (pintype "bidirectional"))
    )
    (net (code "57") (name "Net-(OLED5-VCOMH)") (class "Default")
      (node (ref "C31") (pin "1") (pinfunction "1_1") (pintype "passive"))
      (node (ref "OLED5") (pin "25") (pinfunction "VCOMH_25") (pintype "bidirectional"))
    )
    (net (code "58") (name "Net-(OLED6-C1N)") (class "Default")
      (node (ref "C39") (pin "2") (pinfunction "2_2") (pintype "passive"))
      (node (ref "OLED6") (pin "5") (pinfunction "C1N_5") (pintype "bidirectional"))
    )
    (net (code "59") (name "Net-(OLED6-C1P)") (class "Default")
      (node (ref "C39") (pin "1") (pinfunction "1_1") (pintype "passive"))
      (node (ref "OLED6") (pin "4") (pinfunction "C1P_4") (pintype "bidirectional"))
    )
    (net (code "60") (name "Net-(OLED6-C2N)") (class "Default")
      (node (ref "C38") (pin "2") (pinfunction "2_2") (pintype "passive"))
      (node (ref "OLED6") (pin "3") (pinfunction "C2N_3") (pintype "bidirectional"))
    )
    (net (code "61") (name "Net-(OLED6-C2P)") (class "Default")
      (node (ref "C38") (pin "1") (pinfunction "1_1") (pintype "passive"))
      (node (ref "OLED6") (pin "2") (pinfunction "C2P_2") (pintype "bidirectional"))
    )
    (net (code "62") (name "Net-(OLED6-IREF)") (class "Default")
      (node (ref "OLED6") (pin "24") (pinfunction "IREF_24") (pintype "bidirectional"))
      (node (ref "R7") (pin "1") (pinfunction "1_1") (pintype "passive"))
    )
    (net (code "63") (name "Net-(OLED6-VCC)") (class "Default")
      (node (ref "C37") (pin "1") (pinfunction "1_1") (pintype "passive"))
      (node (ref "OLED6") (pin "26") (pinfunction "VCC_26") (pintype "bidirectional"))
    )
    (net (code "64") (name "Net-(OLED6-VCOMH)") (class "Default")
      (node (ref "C36") (pin "1") (pinfunction "1_1") (pintype "passive"))
      (node (ref "OLED6") (pin "25") (pinfunction "VCOMH_25") (pintype "bidirectional"))
    )
    (net (code "65") (name "Net-(OLED7-C1N)") (class "Default")
      (node (ref "C44") (pin "2") (pinfunction "2_2") (pintype "passive"))
      (node (ref "OLED7") (pin "5") (pinfunction "C1N_5") (pintype "bidirectional"))
    )
    (net (code "66") (name "Net-(OLED7-C1P)") (class "Default")
      (node (ref "C44") (pin "1") (pinfunction "1_1") (pintype "passive"))
      (node (ref "OLED7") (pin "4") (pinfunction "C1P_4") (pintype "bidirectional"))
    )
    (net (code "67") (name "Net-(OLED7-C2N)") (class "Default")
      (node (ref "C43") (pin "2") (pinfunction "2_2") (pintype "passive"))
      (node (ref "OLED7") (pin "3") (pinfunction "C2N_3") (pintype "bidirectional"))
    )
    (net (code "68") (name "Net-(OLED7-C2P)") (class "Default")
      (node (ref "C43") (pin "1") (pinfunction "1_1") (pintype "passive"))
      (node (ref "OLED7") (pin "2") (pinfunction "C2P_2") (pintype "bidirectional"))
    )
    (net (code "69") (name "Net-(OLED7-IREF)") (class "Default")
      (node (ref "OLED7") (pin "24") (pinfunction "IREF_24") (pintype "bidirectional"))
      (node (ref "R9") (pin "1") (pinfunction "1_1") (pintype "passive"))
    )
    (net (code "70") (name "Net-(OLED7-VCC)") (class "Default")
      (node (ref "C42") (pin "1") (pinfunction "1_1") (pintype "passive"))
      (node (ref "OLED7") (pin "26") (pinfunction "VCC_26") (pintype "bidirectional"))
    )
    (net (code "71") (name "Net-(OLED7-VCOMH)") (class "Default")
      (node (ref "C41") (pin "1") (pinfunction "1_1") (pintype "passive"))
      (node (ref "OLED7") (pin "25") (pinfunction "VCOMH_25") (pintype "bidirectional"))
    )
    (net (code "72") (name "Net-(OLED8-C1N)") (class "Default")
      (node (ref "C49") (pin "2") (pinfunction "2_2") (pintype "passive"))
      (node (ref "OLED8") (pin "5") (pinfunction "C1N_5") (pintype "bidirectional"))
    )
    (net (code "73") (name "Net-(OLED8-C1P)") (class "Default")
      (node (ref "C49") (pin "1") (pinfunction "1_1") (pintype "passive"))
      (node (ref "OLED8") (pin "4") (pinfunction "C1P_4") (pintype "bidirectional"))
    )
    (net (code "74") (name "Net-(OLED8-C2N)") (class "Default")
      (node (ref "C48") (pin "2") (pinfunction "2_2") (pintype "passive"))
      (node (ref "OLED8") (pin "3") (pinfunction "C2N_3") (pintype "bidirectional"))
    )
    (net (code "75") (name "Net-(OLED8-C2P)") (class "Default")
      (node (ref "C48") (pin "1") (pinfunction "1_1") (pintype "passive"))
      (node (ref "OLED8") (pin "2") (pinfunction "C2P_2") (pintype "bidirectional"))
    )
    (net (code "76") (name "Net-(OLED8-IREF)") (class "Default")
      (node (ref "OLED8") (pin "24") (pinfunction "IREF_24") (pintype "bidirectional"))
      (node (ref "R10") (pin "1") (pinfunction "1_1") (pintype "passive"))
    )
    (net (code "77") (name "Net-(OLED8-VCC)") (class "Default")
      (node (ref "C47") (pin "1") (pinfunction "1_1") (pintype "passive"))
      (node (ref "OLED8") (pin "26") (pinfunction "VCC_26") (pintype "bidirectional"))
    )
    (net (code "78") (name "Net-(OLED8-VCOMH)") (class "Default")
      (node (ref "C46") (pin "1") (pinfunction "1_1") (pintype "passive"))
      (node (ref "OLED8") (pin "25") (pinfunction "VCOMH_25") (pintype "bidirectional"))
    )
    (net (code "79") (name "Net-(OLED9-C1N)") (class "Default")
      (node (ref "C54") (pin "2") (pinfunction "2_2") (pintype "passive"))
      (node (ref "OLED9") (pin "5") (pinfunction "C1N_5") (pintype "bidirectional"))
    )
    (net (code "80") (name "Net-(OLED9-C1P)") (class "Default")
      (node (ref "C54") (pin "1") (pinfunction "1_1") (pintype "passive"))
      (node (ref "OLED9") (pin "4") (pinfunction "C1P_4") (pintype "bidirectional"))
    )
    (net (code "81") (name "Net-(OLED9-C2N)") (class "Default")
      (node (ref "C53") (pin "2") (pinfunction "2_2") (pintype "passive"))
      (node (ref "OLED9") (pin "3") (pinfunction "C2N_3") (pintype "bidirectional"))
    )
    (net (code "82") (name "Net-(OLED9-C2P)") (class "Default")
      (node (ref "C53") (pin "1") (pinfunction "1_1") (pintype "passive"))
      (node (ref "OLED9") (pin "2") (pinfunction "C2P_2") (pintype "bidirectional"))
    )
    (net (code "83") (name "Net-(OLED9-IREF)") (class "Default")
      (node (ref "OLED9") (pin "24") (pinfunction "IREF_24") (pintype "bidirectional"))
      (node (ref "R11") (pin "1") (pinfunction "1_1") (pintype "passive"))
    )
    (net (code "84") (name "Net-(OLED9-VCC)") (class "Default")
      (node (ref "C52") (pin "1") (pinfunction "1_1") (pintype "passive"))
      (node (ref "OLED9") (pin "26") (pinfunction "VCC_26") (pintype "bidirectional"))
    )
    (net (code "85") (name "Net-(OLED9-VCOMH)") (class "Default")
      (node (ref "C51") (pin "1") (pinfunction "1_1") (pintype "passive"))
      (node (ref "OLED9") (pin "25") (pinfunction "VCOMH_25") (pintype "bidirectional"))
    )
    (net (code "86") (name "Net-(R17-Pad1)") (class "Default")
      (node (ref "R17") (pin "1") (pinfunction "1_1") (pintype "passive"))
      (node (ref "SJ1") (pin "2") (pinfunction "2_2") (pintype "passive"))
    )
    (net (code "87") (name "Net-(R18-Pad1)") (class "Default")
      (node (ref "R18") (pin "1") (pinfunction "1_1") (pintype "passive"))
      (node (ref "SJ2") (pin "2") (pinfunction "2_2") (pintype "passive"))
    )
    (net (code "88") (name "Net-(SW10-S)") (class "Default")
      (node (ref "R16") (pin "2") (pinfunction "2_2") (pintype "passive"))
      (node (ref "SW10") (pin "B") (pinfunction "S_B") (pintype "passive"))
      (node (ref "SW10") (pin "B'") (pinfunction "S1_B'") (pintype "passive"))
    )
    (net (code "89") (name "OSC_IN") (class "Default")
      (node (ref "C6") (pin "2") (pinfunction "2_2") (pintype "passive"))
      (node (ref "OSC") (pin "1") (pinfunction "1_1") (pintype "passive"))
      (node (ref "UC1") (pin "5") (pinfunction "PD0-OSC_IN_5") (pintype "input"))
    )
    (net (code "90") (name "OSC_OUT") (class "Default")
      (node (ref "C7") (pin "2") (pinfunction "2_2") (pintype "passive"))
      (node (ref "OSC") (pin "3") (pinfunction "2_3") (pintype "passive"))
      (node (ref "UC1") (pin "6") (pinfunction "PD1-OSC_OUT_6") (pintype "input"))
    )
    (net (code "91") (name "RESET") (class "Default")
      (node (ref "R8") (pin "1") (pinfunction "1_1") (pintype "passive"))
      (node (ref "SW10") (pin "A") (pinfunction "P_A") (pintype "passive"))
      (node (ref "SW10") (pin "A'") (pinfunction "P1_A'") (pintype "passive"))
      (node (ref "UC1") (pin "7") (pinfunction "NRST_7") (pintype "input"))
    )
    (net (code "92") (name "SCK") (class "Default")
      (node (ref "OLED1") (pin "16") (pinfunction "D0/SCK_16") (pintype "bidirectional"))
      (node (ref "OLED2") (pin "16") (pinfunction "D0/SCK_16") (pintype "bidirectional"))
      (node (ref "OLED3") (pin "16") (pinfunction "D0/SCK_16") (pintype "bidirectional"))
      (node (ref "OLED4") (pin "16") (pinfunction "D0/SCK_16") (pintype "bidirectional"))
      (node (ref "OLED5") (pin "16") (pinfunction "D0/SCK_16") (pintype "bidirectional"))
      (node (ref "OLED6") (pin "16") (pinfunction "D0/SCK_16") (pintype "bidirectional"))
      (node (ref "OLED7") (pin "16") (pinfunction "D0/SCK_16") (pintype "bidirectional"))
      (node (ref "OLED8") (pin "16") (pinfunction "D0/SCK_16") (pintype "bidirectional"))
      (node (ref "OLED9") (pin "16") (pinfunction "D0/SCK_16") (pintype "bidirectional"))
      (node (ref "UC1") (pin "15") (pinfunction "PA5/SPI1_SCK/ADC12_IN5_15") (pintype "bidirectional"))
    )
    (net (code "93") (name "SW01") (class "Default")
      (node (ref "SW1") (pin "A") (pinfunction "P_A") (pintype "passive"))
      (node (ref "SW1") (pin "A'") (pinfunction "P1_A'") (pintype "passive"))
      (node (ref "UC1") (pin "13") (pinfunction "PA3/USART2_RX/ADC12_IN3/TIM2_CH4_13") (pintype "bidirectional"))
    )
    (net (code "94") (name "SW02") (class "Default")
      (node (ref "SW2") (pin "A") (pinfunction "P_A") (pintype "passive"))
      (node (ref "UC1") (pin "18") (pinfunction "PB0/ADC12_IN8/TIM3_CH3_18") (pintype "bidirectional"))
    )
    (net (code "95") (name "SW03") (class "Default")
      (node (ref "SW3") (pin "A") (pinfunction "P_A") (pintype "passive"))
      (node (ref "SW3") (pin "A'") (pinfunction "P1_A'") (pintype "passive"))
      (node (ref "UC1") (pin "25") (pinfunction "PB12/SPI2_NSS/I2C2_SMBA/USART3_CK/TIM1_BKIN_25") (pintype "input"))
    )
    (net (code "96") (name "SW04") (class "Default")
      (node (ref "SW4") (pin "A") (pinfunction "P_A") (pintype "passive"))
      (node (ref "SW4") (pin "A'") (pinfunction "P1_A'") (pintype "passive"))
      (node (ref "UC1") (pin "38") (pinfunction "PA15/JTDI_38") (pintype "bidirectional"))
    )
    (net (code "97") (name "SW05") (class "Default")
      (node (ref "SW5") (pin "A") (pinfunction "P_A") (pintype "passive"))
      (node (ref "SW5") (pin "A'") (pinfunction "P1_A'") (pintype "passive"))
      (node (ref "UC1") (pin "22") (pinfunction "PB11/I2C2_SDA/USART3_RX_22") (pintype "input"))
    )
    (net (code "98") (name "SW06") (class "Default")
      (node (ref "SW6") (pin "A") (pinfunction "P_A") (pintype "passive"))
      (node (ref "SW6") (pin "A'") (pinfunction "P1_A'") (pintype "passive"))
      (node (ref "UC1") (pin "30") (pinfunction "PA9/USART1_TX/TIM1_CH2_30") (pintype "input"))
    )
    (net (code "99") (name "SW07") (class "Default")
      (node (ref "SW7") (pin "A") (pinfunction "P_A") (pintype "passive"))
      (node (ref "SW7") (pin "A'") (pinfunction "P1_A'") (pintype "passive"))
      (node (ref "UC1") (pin "37") (pinfunction "PA14/JTCK/SWCLK_37") (pintype "bidirectional"))
    )
    (net (code "100") (name "SW08") (class "Default")
      (node (ref "SW8") (pin "A") (pinfunction "P_A") (pintype "passive"))
      (node (ref "SW8") (pin "A'") (pinfunction "P1_A'") (pintype "passive"))
      (node (ref "UC1") (pin "21") (pinfunction "PB10/I2C2_SCL/USART3_TX_21") (pintype "input"))
    )
    (net (code "101") (name "SW09") (class "Default")
      (node (ref "SW9") (pin "A") (pinfunction "P_A") (pintype "passive"))
      (node (ref "SW9") (pin "A'") (pinfunction "P1_A'") (pintype "passive"))
      (node (ref "UC1") (pin "29") (pinfunction "PA8/USART1_CK/TIM1_CH1/MCO_29") (pintype "bidirectional"))
    )
    (net (code "102") (name "UART1_RX") (class "Default")
      (node (ref "UC1") (pin "31") (pinfunction "PA10/USART1_RX/TIM1_CH3_31") (pintype "bidirectional"))
    )
    (net (code "103") (name "USBDM") (class "Default")
      (node (ref "C12") (pin "1") (pinfunction "1_1") (pintype "passive"))
      (node (ref "R14") (pin "2") (pinfunction "2_2") (pintype "passive"))
      (node (ref "UC1") (pin "32") (pinfunction "PA11/USART1_CTS/CAN_RX/TIM1_CH4/USBDM_32") (pintype "bidirectional"))
    )
    (net (code "104") (name "USBDP") (class "Default")
      (node (ref "C13") (pin "1") (pinfunction "1_1") (pintype "passive"))
      (node (ref "R13") (pin "2") (pinfunction "2_2") (pintype "passive"))
      (node (ref "R20") (pin "1") (pinfunction "1_1") (pintype "passive"))
      (node (ref "UC1") (pin "33") (pinfunction "PA12/USART1_RTS/CAN_TX/TIM1_ETR/USBDP_33") (pintype "bidirectional"))
    )
    (net (code "105") (name "V_USB") (class "Default")
      (node (ref "C8") (pin "1") (pinfunction "1_1") (pintype "passive"))
      (node (ref "F1") (pin "2") (pinfunction "2_2") (pintype "bidirectional"))
      (node (ref "U3") (pin "1") (pinfunction "IN_1") (pintype "input"))
      (node (ref "U3") (pin "3") (pinfunction "EN_3") (pintype "input"))
    )
    (net (code "106") (name "unconnected-(OLED1-D2-Pad18)") (class "Default")
      (node (ref "OLED1") (pin "18") (pinfunction "D2_18") (pintype "bidirectional"))
    )
    (net (code "107") (name "unconnected-(OLED1-D3-Pad19)") (class "Default")
      (node (ref "OLED1") (pin "19") (pinfunction "D3_19") (pintype "bidirectional"))
    )
    (net (code "108") (name "unconnected-(OLED1-D4-Pad20)") (class "Default")
      (node (ref "OLED1") (pin "20") (pinfunction "D4_20") (pintype "bidirectional"))
    )
    (net (code "109") (name "unconnected-(OLED1-D5-Pad21)") (class "Default")
      (node (ref "OLED1") (pin "21") (pinfunction "D5_21") (pintype "bidirectional"))
    )
    (net (code "110") (name "unconnected-(OLED1-D6-Pad22)") (class "Default")
      (node (ref "OLED1") (pin "22") (pinfunction "D6_22") (pintype "bidirectional"))
    )
    (net (code "111") (name "unconnected-(OLED1-D7-Pad23)") (class "Default")
      (node (ref "OLED1") (pin "23") (pinfunction "D7_23") (pintype "bidirectional"))
    )
    (net (code "112") (name "unconnected-(OLED1-E{slash}~{RD}-Pad15)") (class "Default")
      (node (ref "OLED1") (pin "15") (pinfunction "E/~{RD}_15") (pintype "bidirectional"))
    )
    (net (code "113") (name "unconnected-(OLED1-R{slash}~{W}-Pad14)") (class "Default")
      (node (ref "OLED1") (pin "14") (pinfunction "R/~{W}_14") (pintype "bidirectional"))
    )
    (net (code "114") (name "unconnected-(OLED2-D2-Pad18)") (class "Default")
      (node (ref "OLED2") (pin "18") (pinfunction "D2_18") (pintype "bidirectional"))
    )
    (net (code "115") (name "unconnected-(OLED2-D3-Pad19)") (class "Default")
      (node (ref "OLED2") (pin "19") (pinfunction "D3_19") (pintype "bidirectional"))
    )
    (net (code "116") (name "unconnected-(OLED2-D4-Pad20)") (class "Default")
      (node (ref "OLED2") (pin "20") (pinfunction "D4_20") (pintype "bidirectional"))
    )
    (net (code "117") (name "unconnected-(OLED2-D5-Pad21)") (class "Default")
      (node (ref "OLED2") (pin "21") (pinfunction "D5_21") (pintype "bidirectional"))
    )
    (net (code "118") (name "unconnected-(OLED2-D6-Pad22)") (class "Default")
      (node (ref "OLED2") (pin "22") (pinfunction "D6_22") (pintype "bidirectional"))
    )
    (net (code "119") (name "unconnected-(OLED2-D7-Pad23)") (class "Default")
      (node (ref "OLED2") (pin "23") (pinfunction "D7_23") (pintype "bidirectional"))
    )
    (net (code "120") (name "unconnected-(OLED2-E{slash}~{RD}-Pad15)") (class "Default")
      (node (ref "OLED2") (pin "15") (pinfunction "E/~{RD}_15") (pintype "bidirectional"))
    )
    (net (code "121") (name "unconnected-(OLED2-R{slash}~{W}-Pad14)") (class "Default")
      (node (ref "OLED2") (pin "14") (pinfunction "R/~{W}_14") (pintype "bidirectional"))
    )
    (net (code "122") (name "unconnected-(OLED3-D2-Pad18)") (class "Default")
      (node (ref "OLED3") (pin "18") (pinfunction "D2_18") (pintype "bidirectional"))
    )
    (net (code "123") (name "unconnected-(OLED3-D3-Pad19)") (class "Default")
      (node (ref "OLED3") (pin "19") (pinfunction "D3_19") (pintype "bidirectional"))
    )
    (net (code "124") (name "unconnected-(OLED3-D4-Pad20)") (class "Default")
      (node (ref "OLED3") (pin "20") (pinfunction "D4_20") (pintype "bidirectional"))
    )
    (net (code "125") (name "unconnected-(OLED3-D5-Pad21)") (class "Default")
      (node (ref "OLED3") (pin "21") (pinfunction "D5_21") (pintype "bidirectional"))
    )
    (net (code "126") (name "unconnected-(OLED3-D6-Pad22)") (class "Default")
      (node (ref "OLED3") (pin "22") (pinfunction "D6_22") (pintype "bidirectional"))
    )
    (net (code "127") (name "unconnected-(OLED3-D7-Pad23)") (class "Default")
      (node (ref "OLED3") (pin "23") (pinfunction "D7_23") (pintype "bidirectional"))
    )
    (net (code "128") (name "unconnected-(OLED3-E{slash}~{RD}-Pad15)") (class "Default")
      (node (ref "OLED3") (pin "15") (pinfunction "E/~{RD}_15") (pintype "bidirectional"))
    )
    (net (code "129") (name "unconnected-(OLED3-R{slash}~{W}-Pad14)") (class "Default")
      (node (ref "OLED3") (pin "14") (pinfunction "R/~{W}_14") (pintype "bidirectional"))
    )
    (net (code "130") (name "unconnected-(OLED4-D2-Pad18)") (class "Default")
      (node (ref "OLED4") (pin "18") (pinfunction "D2_18") (pintype "bidirectional"))
    )
    (net (code "131") (name "unconnected-(OLED4-D3-Pad19)") (class "Default")
      (node (ref "OLED4") (pin "19") (pinfunction "D3_19") (pintype "bidirectional"))
    )
    (net (code "132") (name "unconnected-(OLED4-D4-Pad20)") (class "Default")
      (node (ref "OLED4") (pin "20") (pinfunction "D4_20") (pintype "bidirectional"))
    )
    (net (code "133") (name "unconnected-(OLED4-D5-Pad21)") (class "Default")
      (node (ref "OLED4") (pin "21") (pinfunction "D5_21") (pintype "bidirectional"))
    )
    (net (code "134") (name "unconnected-(OLED4-D6-Pad22)") (class "Default")
      (node (ref "OLED4") (pin "22") (pinfunction "D6_22") (pintype "bidirectional"))
    )
    (net (code "135") (name "unconnected-(OLED4-D7-Pad23)") (class "Default")
      (node (ref "OLED4") (pin "23") (pinfunction "D7_23") (pintype "bidirectional"))
    )
    (net (code "136") (name "unconnected-(OLED4-E{slash}~{RD}-Pad15)") (class "Default")
      (node (ref "OLED4") (pin "15") (pinfunction "E/~{RD}_15") (pintype "bidirectional"))
    )
    (net (code "137") (name "unconnected-(OLED4-R{slash}~{W}-Pad14)") (class "Default")
      (node (ref "OLED4") (pin "14") (pinfunction "R/~{W}_14") (pintype "bidirectional"))
    )
    (net (code "138") (name "unconnected-(OLED5-D2-Pad18)") (class "Default")
      (node (ref "OLED5") (pin "18") (pinfunction "D2_18") (pintype "bidirectional"))
    )
    (net (code "139") (name "unconnected-(OLED5-D3-Pad19)") (class "Default")
      (node (ref "OLED5") (pin "19") (pinfunction "D3_19") (pintype "bidirectional"))
    )
    (net (code "140") (name "unconnected-(OLED5-D4-Pad20)") (class "Default")
      (node (ref "OLED5") (pin "20") (pinfunction "D4_20") (pintype "bidirectional"))
    )
    (net (code "141") (name "unconnected-(OLED5-D5-Pad21)") (class "Default")
      (node (ref "OLED5") (pin "21") (pinfunction "D5_21") (pintype "bidirectional"))
    )
    (net (code "142") (name "unconnected-(OLED5-D6-Pad22)") (class "Default")
      (node (ref "OLED5") (pin "22") (pinfunction "D6_22") (pintype "bidirectional"))
    )
    (net (code "143") (name "unconnected-(OLED5-D7-Pad23)") (class "Default")
      (node (ref "OLED5") (pin "23") (pinfunction "D7_23") (pintype "bidirectional"))
    )
    (net (code "144") (name "unconnected-(OLED5-E{slash}~{RD}-Pad15)") (class "Default")
      (node (ref "OLED5") (pin "15") (pinfunction "E/~{RD}_15") (pintype "bidirectional"))
    )
    (net (code "145") (name "unconnected-(OLED5-R{slash}~{W}-Pad14)") (class "Default")
      (node (ref "OLED5") (pin "14") (pinfunction "R/~{W}_14") (pintype "bidirectional"))
    )
    (net (code "146") (name "unconnected-(OLED6-D2-Pad18)") (class "Default")
      (node (ref "OLED6") (pin "18") (pinfunction "D2_18") (pintype "bidirectional"))
    )
    (net (code "147") (name "unconnected-(OLED6-D3-Pad19)") (class "Default")
      (node (ref "OLED6") (pin "19") (pinfunction "D3_19") (pintype "bidirectional"))
    )
    (net (code "148") (name "unconnected-(OLED6-D4-Pad20)") (class "Default")
      (node (ref "OLED6") (pin "20") (pinfunction "D4_20") (pintype "bidirectional"))
    )
    (net (code "149") (name "unconnected-(OLED6-D5-Pad21)") (class "Default")
      (node (ref "OLED6") (pin "21") (pinfunction "D5_21") (pintype "bidirectional"))
    )
    (net (code "150") (name "unconnected-(OLED6-D6-Pad22)") (class "Default")
      (node (ref "OLED6") (pin "22") (pinfunction "D6_22") (pintype "bidirectional"))
    )
    (net (code "151") (name "unconnected-(OLED6-D7-Pad23)") (class "Default")
      (node (ref "OLED6") (pin "23") (pinfunction "D7_23") (pintype "bidirectional"))
    )
    (net (code "152") (name "unconnected-(OLED6-E{slash}~{RD}-Pad15)") (class "Default")
      (node (ref "OLED6") (pin "15") (pinfunction "E/~{RD}_15") (pintype "bidirectional"))
    )
    (net (code "153") (name "unconnected-(OLED6-R{slash}~{W}-Pad14)") (class "Default")
      (node (ref "OLED6") (pin "14") (pinfunction "R/~{W}_14") (pintype "bidirectional"))
    )
    (net (code "154") (name "unconnected-(OLED7-D2-Pad18)") (class "Default")
      (node (ref "OLED7") (pin "18") (pinfunction "D2_18") (pintype "bidirectional"))
    )
    (net (code "155") (name "unconnected-(OLED7-D3-Pad19)") (class "Default")
      (node (ref "OLED7") (pin "19") (pinfunction "D3_19") (pintype "bidirectional"))
    )
    (net (code "156") (name "unconnected-(OLED7-D4-Pad20)") (class "Default")
      (node (ref "OLED7") (pin "20") (pinfunction "D4_20") (pintype "bidirectional"))
    )
    (net (code "157") (name "unconnected-(OLED7-D5-Pad21)") (class "Default")
      (node (ref "OLED7") (pin "21") (pinfunction "D5_21") (pintype "bidirectional"))
    )
    (net (code "158") (name "unconnected-(OLED7-D6-Pad22)") (class "Default")
      (node (ref "OLED7") (pin "22") (pinfunction "D6_22") (pintype "bidirectional"))
    )
    (net (code "159") (name "unconnected-(OLED7-D7-Pad23)") (class "Default")
      (node (ref "OLED7") (pin "23") (pinfunction "D7_23") (pintype "bidirectional"))
    )
    (net (code "160") (name "unconnected-(OLED7-E{slash}~{RD}-Pad15)") (class "Default")
      (node (ref "OLED7") (pin "15") (pinfunction "E/~{RD}_15") (pintype "bidirectional"))
    )
    (net (code "161") (name "unconnected-(OLED7-R{slash}~{W}-Pad14)") (class "Default")
      (node (ref "OLED7") (pin "14") (pinfunction "R/~{W}_14") (pintype "bidirectional"))
    )
    (net (code "162") (name "unconnected-(OLED8-D2-Pad18)") (class "Default")
      (node (ref "OLED8") (pin "18") (pinfunction "D2_18") (pintype "bidirectional"))
    )
    (net (code "163") (name "unconnected-(OLED8-D3-Pad19)") (class "Default")
      (node (ref "OLED8") (pin "19") (pinfunction "D3_19") (pintype "bidirectional"))
    )
    (net (code "164") (name "unconnected-(OLED8-D4-Pad20)") (class "Default")
      (node (ref "OLED8") (pin "20") (pinfunction "D4_20") (pintype "bidirectional"))
    )
    (net (code "165") (name "unconnected-(OLED8-D5-Pad21)") (class "Default")
      (node (ref "OLED8") (pin "21") (pinfunction "D5_21") (pintype "bidirectional"))
    )
    (net (code "166") (name "unconnected-(OLED8-D6-Pad22)") (class "Default")
      (node (ref "OLED8") (pin "22") (pinfunction "D6_22") (pintype "bidirectional"))
    )
    (net (code "167") (name "unconnected-(OLED8-D7-Pad23)") (class "Default")
      (node (ref "OLED8") (pin "23") (pinfunction "D7_23") (pintype "bidirectional"))
    )
    (net (code "168") (name "unconnected-(OLED8-E{slash}~{RD}-Pad15)") (class "Default")
      (node (ref "OLED8") (pin "15") (pinfunction "E/~{RD}_15") (pintype "bidirectional"))
    )
    (net (code "169") (name "unconnected-(OLED8-R{slash}~{W}-Pad14)") (class "Default")
      (node (ref "OLED8") (pin "14") (pinfunction "R/~{W}_14") (pintype "bidirectional"))
    )
    (net (code "170") (name "unconnected-(OLED9-D2-Pad18)") (class "Default")
      (node (ref "OLED9") (pin "18") (pinfunction "D2_18") (pintype "bidirectional"))
    )
    (net (code "171") (name "unconnected-(OLED9-D3-Pad19)") (class "Default")
      (node (ref "OLED9") (pin "19") (pinfunction "D3_19") (pintype "bidirectional"))
    )
    (net (code "172") (name "unconnected-(OLED9-D4-Pad20)") (class "Default")
      (node (ref "OLED9") (pin "20") (pinfunction "D4_20") (pintype "bidirectional"))
    )
    (net (code "173") (name "unconnected-(OLED9-D5-Pad21)") (class "Default")
      (node (ref "OLED9") (pin "21") (pinfunction "D5_21") (pintype "bidirectional"))
    )
    (net (code "174") (name "unconnected-(OLED9-D6-Pad22)") (class "Default")
      (node (ref "OLED9") (pin "22") (pinfunction "D6_22") (pintype "bidirectional"))
    )
    (net (code "175") (name "unconnected-(OLED9-D7-Pad23)") (class "Default")
      (node (ref "OLED9") (pin "23") (pinfunction "D7_23") (pintype "bidirectional"))
    )
    (net (code "176") (name "unconnected-(OLED9-E{slash}~{RD}-Pad15)") (class "Default")
      (node (ref "OLED9") (pin "15") (pinfunction "E/~{RD}_15") (pintype "bidirectional"))
    )
    (net (code "177") (name "unconnected-(OLED9-R{slash}~{W}-Pad14)") (class "Default")
      (node (ref "OLED9") (pin "14") (pinfunction "R/~{W}_14") (pintype "bidirectional"))
    )
    (net (code "178") (name "unconnected-(SW2-P1-PadA')") (class "Default")
      (node (ref "SW2") (pin "A'") (pinfunction "P1_A'") (pintype "passive"))
    )
    (net (code "179") (name "unconnected-(U3-BP-Pad4)") (class "Default")
      (node (ref "U3") (pin "4") (pinfunction "BP_4") (pintype "input"))
    )
    (net (code "180") (name "unconnected-(UC1-PA0_WKUP{slash}USART2_CTS{slash}ADC12_IN0{slash}TIM2_CH1_ETR-Pad10)") (class "Default")
      (node (ref "UC1") (pin "10") (pinfunction "PA0_WKUP/USART2_CTS/ADC12_IN0/TIM2_CH1_ETR_10") (pintype "bidirectional"))
    )
    (net (code "181") (name "unconnected-(UC1-PA13{slash}JTMS{slash}SWDIO-Pad34)") (class "Default")
      (node (ref "UC1") (pin "34") (pinfunction "PA13/JTMS/SWDIO_34") (pintype "bidirectional"))
    )
    (net (code "182") (name "unconnected-(UC1-PB6{slash}I2C1_SCL{slash}TIM4_CH1-Pad42)") (class "Default")
      (node (ref "UC1") (pin "42") (pinfunction "PB6/I2C1_SCL/TIM4_CH1_42") (pintype "input"))
    )
    (net (code "183") (name "unconnected-(UC1-PB7{slash}I2C1_SDA{slash}TIM4_CH2-Pad43)") (class "Default")
      (node (ref "UC1") (pin "43") (pinfunction "PB7/I2C1_SDA/TIM4_CH2_43") (pintype "bidirectional"))
    )
    (net (code "184") (name "unconnected-(UC1-PB8{slash}TIM4_CH3-Pad45)") (class "Default")
      (node (ref "UC1") (pin "45") (pinfunction "PB8/TIM4_CH3_45") (pintype "bidirectional"))
    )
    (net (code "185") (name "unconnected-(UC1-PB9{slash}TIM4_CH4-Pad46)") (class "Default")
      (node (ref "UC1") (pin "46") (pinfunction "PB9/TIM4_CH4_46") (pintype "input"))
    )
    (net (code "186") (name "unconnected-(UC1-PC13-TAMPER-RTC-Pad2)") (class "Default")
      (node (ref "UC1") (pin "2") (pinfunction "PC13-TAMPER-RTC_2") (pintype "input"))
    )
    (net (code "187") (name "unconnected-(UC1-PC14-OSC32_IN-Pad3)") (class "Default")
      (node (ref "UC1") (pin "3") (pinfunction "PC14-OSC32_IN_3") (pintype "input"))
    )
    (net (code "188") (name "unconnected-(UC1-PC15-OSC32_OUT-Pad4)") (class "Default")
      (node (ref "UC1") (pin "4") (pinfunction "PC15-OSC32_OUT_4") (pintype "input"))
    )
  )
)
